# ShifterBit.net
KiCad netlist of a schematic drawn in EAGLE
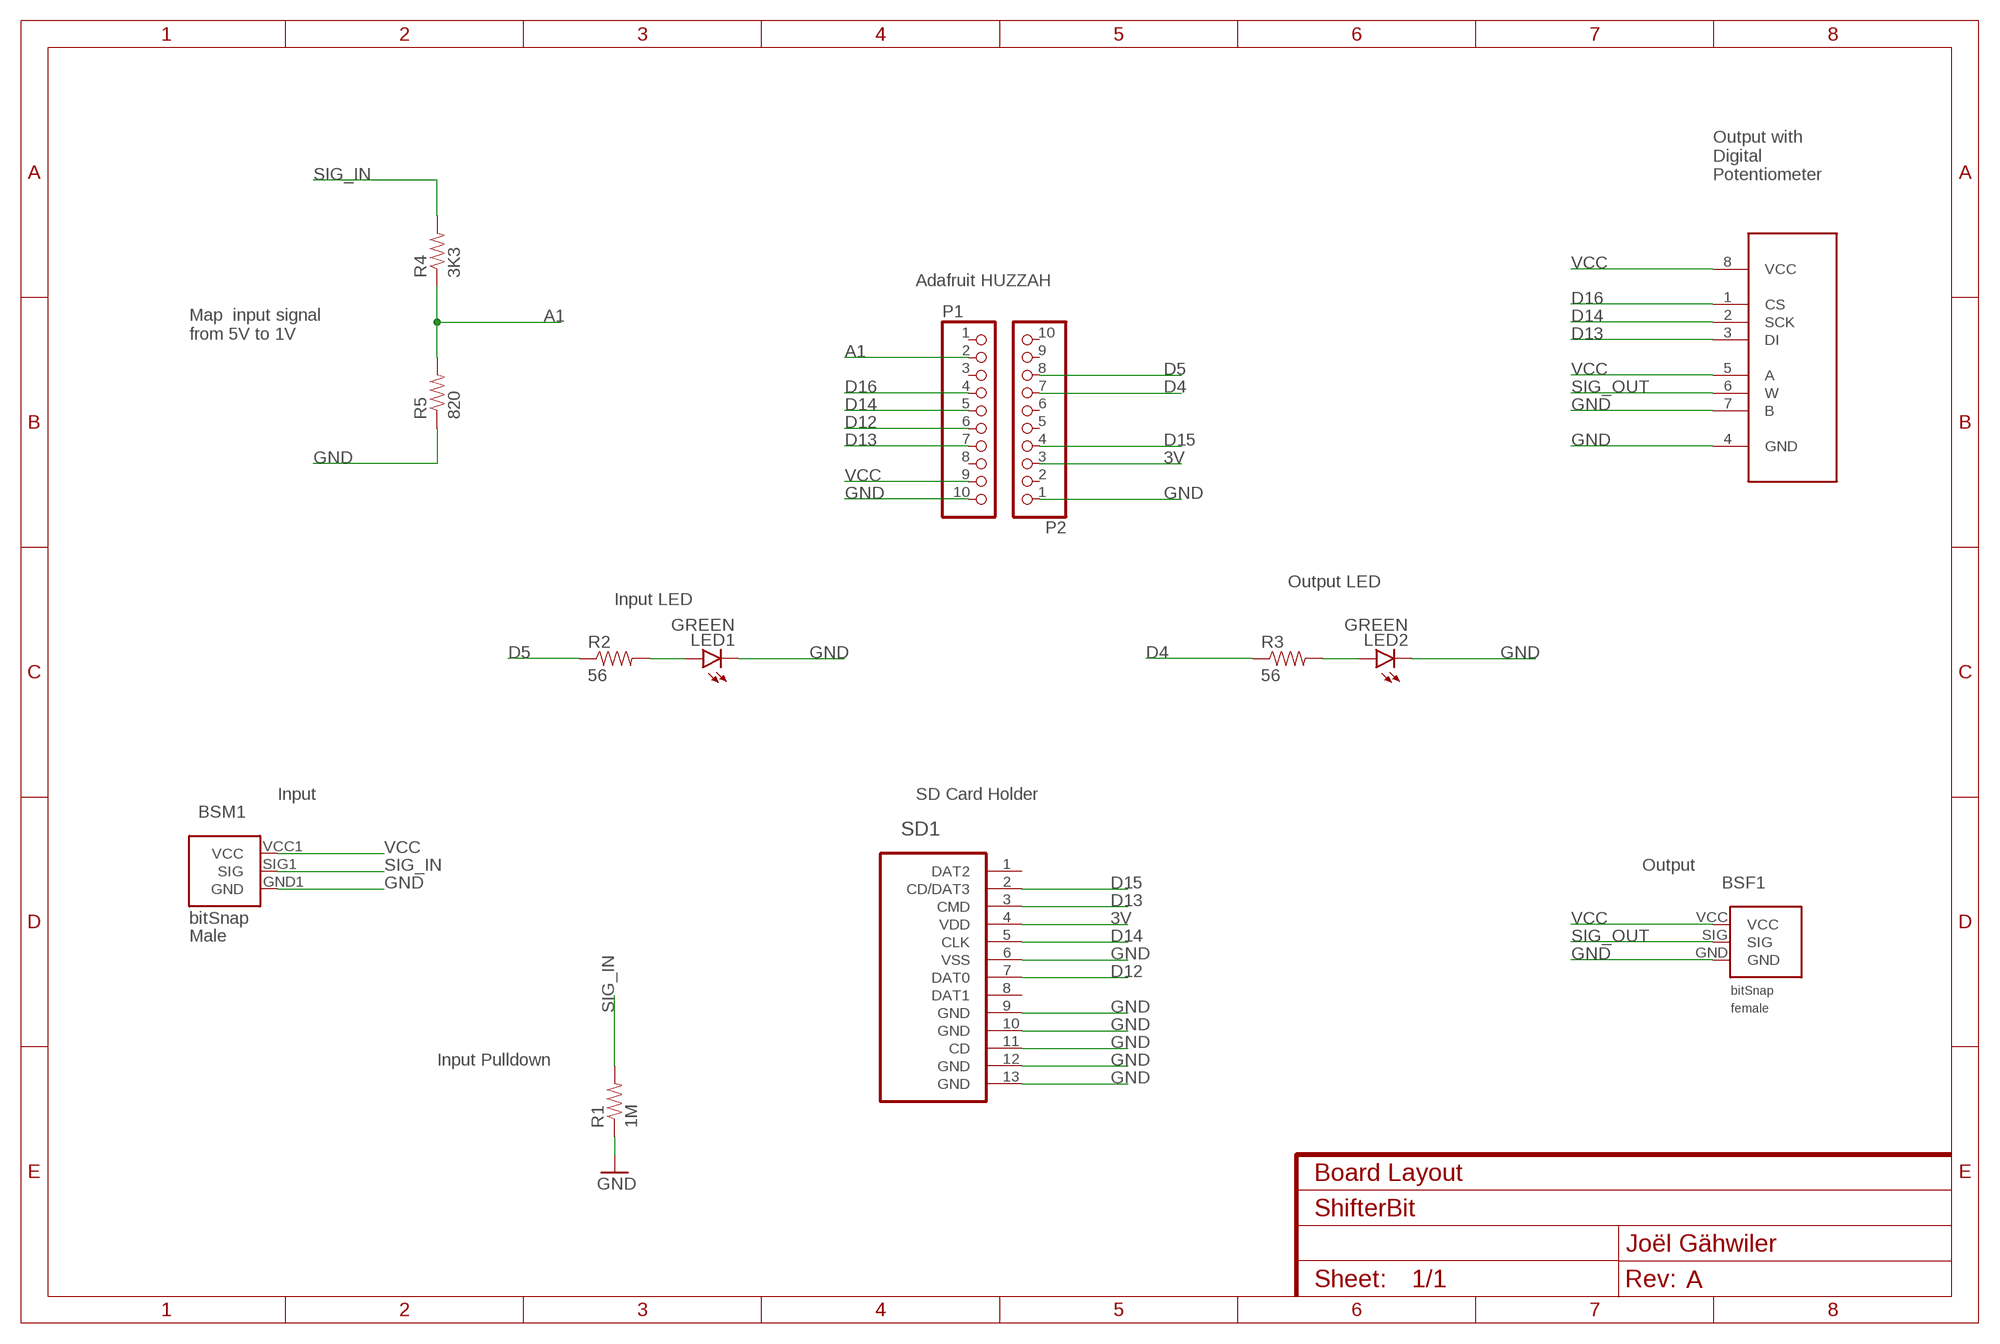
[diagram p0: schematic, sheet 1]

(export (version "E")
  (design (tool "Eeschema 10.0.6"))
  (components
    (comp (ref "BSF1")
      (value "BITSNAP_V03_FEMALE")
      (footprint "eagle-import:BITSNAP_V03_FEMALE")
      (libsource (lib "eagle-import") (part "BITSNAP_V03_FEMALE"))
    )
    (comp (ref "BSM1")
      (value "BITSNAP_V03_MALE")
      (footprint "eagle-import:BITSNAP_V03_MALE")
      (libsource (lib "eagle-import") (part "BITSNAP_V03_MALE"))
    )
    (comp (ref "DPOT1")
      (value "MCP41XXX")
      (footprint "eagle-import:SO08")
      (libsource (lib "eagle-import") (part "MCP41XXX"))
    )
    (comp (ref "LED1")
      (value "GREEN")
      (footprint "eagle-import:LED-1206")
      (libsource (lib "eagle-import") (part "LED-GREENLARGE"))
    )
    (comp (ref "LED2")
      (value "GREEN")
      (footprint "eagle-import:LED-1206")
      (libsource (lib "eagle-import") (part "LED-GREENLARGE"))
    )
    (comp (ref "P1")
      (value "PINHD-1X10")
      (footprint "eagle-import:1X10-BIG")
      (libsource (lib "eagle-import") (part "PINHD-1X10"))
    )
    (comp (ref "P2")
      (value "PINHD-1X10")
      (footprint "eagle-import:1X10-BIG")
      (libsource (lib "eagle-import") (part "PINHD-1X10"))
    )
    (comp (ref "R1")
      (value "1M")
      (footprint "eagle-import:RES-1206")
      (libsource (lib "eagle-import") (part "RESISTOR1206"))
    )
    (comp (ref "R2")
      (value "56")
      (footprint "eagle-import:1206")
      (libsource (lib "eagle-import") (part "SparkFun-Passives_RESISTOR1206"))
    )
    (comp (ref "R3")
      (value "56")
      (footprint "eagle-import:1206")
      (libsource (lib "eagle-import") (part "SparkFun-Passives_RESISTOR1206"))
    )
    (comp (ref "R4")
      (value "3K3")
      (footprint "eagle-import:1206")
      (libsource (lib "eagle-import") (part "SparkFun-Passives_RESISTOR1206"))
    )
    (comp (ref "R5")
      (value "820")
      (footprint "eagle-import:1206")
      (libsource (lib "eagle-import") (part "SparkFun-Passives_RESISTOR1206"))
    )
    (comp (ref "SD1")
      (value "HIROSE_DM3CS-SF")
      (footprint "eagle-import:HIROSE_DM3CS-SF")
      (fields (field (name "MPN") "DM3CS-SF"))
      (libsource (lib "eagle-import") (part "HIROSE_DM3CS-SF"))
    )
  )
  (nets
    (net (code "1") (name "/3V") (class "Default")
      (node (ref "P2") (pin "3") (pinfunction "3_3") (pintype "passive"))
      (node (ref "SD1") (pin "4") (pinfunction "VDD_4") (pintype "passive"))
    )
    (net (code "2") (name "/A1") (class "Default")
      (node (ref "P1") (pin "2") (pinfunction "2_2") (pintype "passive"))
      (node (ref "R4") (pin "1") (pinfunction "1_1") (pintype "passive"))
      (node (ref "R5") (pin "2") (pinfunction "2_2") (pintype "passive"))
    )
    (net (code "3") (name "/D4") (class "Default")
      (node (ref "P2") (pin "7") (pinfunction "7_7") (pintype "passive"))
      (node (ref "R3") (pin "1") (pinfunction "1_1") (pintype "passive"))
    )
    (net (code "4") (name "/D5") (class "Default")
      (node (ref "P2") (pin "8") (pinfunction "8_8") (pintype "passive"))
      (node (ref "R2") (pin "1") (pinfunction "1_1") (pintype "passive"))
    )
    (net (code "5") (name "/D12") (class "Default")
      (node (ref "P1") (pin "6") (pinfunction "6_6") (pintype "passive"))
      (node (ref "SD1") (pin "7") (pinfunction "DAT0_7") (pintype "passive"))
    )
    (net (code "6") (name "/D13") (class "Default")
      (node (ref "DPOT1") (pin "3") (pinfunction "DI_3") (pintype "bidirectional"))
      (node (ref "P1") (pin "7") (pinfunction "7_7") (pintype "passive"))
      (node (ref "SD1") (pin "3") (pinfunction "CMD_3") (pintype "passive"))
    )
    (net (code "7") (name "/D14") (class "Default")
      (node (ref "DPOT1") (pin "2") (pinfunction "SCK_2") (pintype "bidirectional"))
      (node (ref "P1") (pin "5") (pinfunction "5_5") (pintype "passive"))
      (node (ref "SD1") (pin "5") (pinfunction "CLK_5") (pintype "passive"))
    )
    (net (code "8") (name "/D15") (class "Default")
      (node (ref "P2") (pin "4") (pinfunction "4_4") (pintype "passive"))
      (node (ref "SD1") (pin "2") (pinfunction "CD/DAT3_2") (pintype "passive"))
    )
    (net (code "9") (name "/D16") (class "Default")
      (node (ref "DPOT1") (pin "1") (pinfunction "CS_1") (pintype "bidirectional"))
      (node (ref "P1") (pin "4") (pinfunction "4_4") (pintype "passive"))
    )
    (net (code "10") (name "/SIG_IN") (class "Default")
      (node (ref "BSM1") (pin "SIG1") (pinfunction "SIG_SIG1") (pintype "bidirectional"))
      (node (ref "R1") (pin "2") (pinfunction "2_2") (pintype "passive"))
      (node (ref "R4") (pin "2") (pinfunction "2_2") (pintype "passive"))
    )
    (net (code "11") (name "/SIG_OUT") (class "Default")
      (node (ref "BSF1") (pin "SIG") (pinfunction "SIG_SIG") (pintype "bidirectional"))
      (node (ref "DPOT1") (pin "6") (pinfunction "W_6") (pintype "bidirectional"))
    )
    (net (code "12") (name "/VCC") (class "Default")
      (node (ref "BSF1") (pin "VCC") (pinfunction "VCC_VCC") (pintype "bidirectional"))
      (node (ref "BSM1") (pin "VCC1") (pinfunction "VCC_VCC1") (pintype "bidirectional"))
      (node (ref "DPOT1") (pin "5") (pinfunction "A_5") (pintype "bidirectional"))
      (node (ref "DPOT1") (pin "8") (pinfunction "VCC_8") (pintype "bidirectional"))
      (node (ref "P1") (pin "9") (pinfunction "9_9") (pintype "passive"))
    )
    (net (code "13") (name "GND") (class "Default")
      (node (ref "BSF1") (pin "GND") (pinfunction "GND_GND") (pintype "bidirectional"))
      (node (ref "BSM1") (pin "GND1") (pinfunction "GND_GND1") (pintype "bidirectional"))
      (node (ref "DPOT1") (pin "4") (pinfunction "GND_4") (pintype "bidirectional"))
      (node (ref "DPOT1") (pin "7") (pinfunction "B_7") (pintype "bidirectional"))
      (node (ref "LED1") (pin "C") (pinfunction "C_C") (pintype "passive"))
      (node (ref "LED2") (pin "C") (pinfunction "C_C") (pintype "passive"))
      (node (ref "P1") (pin "10") (pinfunction "10_10") (pintype "passive"))
      (node (ref "P2") (pin "1") (pinfunction "1_1") (pintype "passive"))
      (node (ref "R1") (pin "1") (pinfunction "1_1") (pintype "passive"))
      (node (ref "R5") (pin "1") (pinfunction "1_1") (pintype "passive"))
      (node (ref "SD1") (pin "10") (pinfunction "GND_10") (pintype "passive"))
      (node (ref "SD1") (pin "11") (pinfunction "CD_11") (pintype "passive"))
      (node (ref "SD1") (pin "12") (pinfunction "GND_12") (pintype "passive"))
      (node (ref "SD1") (pin "13") (pinfunction "GND_13") (pintype "passive"))
      (node (ref "SD1") (pin "6") (pinfunction "VSS_6") (pintype "passive"))
      (node (ref "SD1") (pin "9") (pinfunction "GND_9") (pintype "passive"))
    )
    (net (code "14") (name "Net-(LED1-PadA)") (class "Default")
      (node (ref "LED1") (pin "A") (pinfunction "A_A") (pintype "passive"))
      (node (ref "R2") (pin "2") (pinfunction "2_2") (pintype "passive"))
    )
    (net (code "15") (name "Net-(LED2-PadA)") (class "Default")
      (node (ref "LED2") (pin "A") (pinfunction "A_A") (pintype "passive"))
      (node (ref "R3") (pin "2") (pinfunction "2_2") (pintype "passive"))
    )
    (net (code "16") (name "unconnected-(P1-Pad1)") (class "Default")
      (node (ref "P1") (pin "1") (pinfunction "1_1") (pintype "passive"))
    )
    (net (code "17") (name "unconnected-(P1-Pad3)") (class "Default")
      (node (ref "P1") (pin "3") (pinfunction "3_3") (pintype "passive"))
    )
    (net (code "18") (name "unconnected-(P1-Pad8)") (class "Default")
      (node (ref "P1") (pin "8") (pinfunction "8_8") (pintype "passive"))
    )
    (net (code "19") (name "unconnected-(P2-Pad2)") (class "Default")
      (node (ref "P2") (pin "2") (pinfunction "2_2") (pintype "passive"))
    )
    (net (code "20") (name "unconnected-(P2-Pad5)") (class "Default")
      (node (ref "P2") (pin "5") (pinfunction "5_5") (pintype "passive"))
    )
    (net (code "21") (name "unconnected-(P2-Pad6)") (class "Default")
      (node (ref "P2") (pin "6") (pinfunction "6_6") (pintype "passive"))
    )
    (net (code "22") (name "unconnected-(P2-Pad9)") (class "Default")
      (node (ref "P2") (pin "9") (pinfunction "9_9") (pintype "passive"))
    )
    (net (code "23") (name "unconnected-(P2-Pad10)") (class "Default")
      (node (ref "P2") (pin "10") (pinfunction "10_10") (pintype "passive"))
    )
    (net (code "24") (name "unconnected-(SD1-DAT1-Pad8)") (class "Default")
      (node (ref "SD1") (pin "8") (pinfunction "DAT1_8") (pintype "passive"))
    )
    (net (code "25") (name "unconnected-(SD1-DAT2-Pad1)") (class "Default")
      (node (ref "SD1") (pin "1") (pinfunction "DAT2_1") (pintype "passive"))
    )
  )
)
